# pomodoro.net
KiCad netlist of a schematic drawn in EAGLE
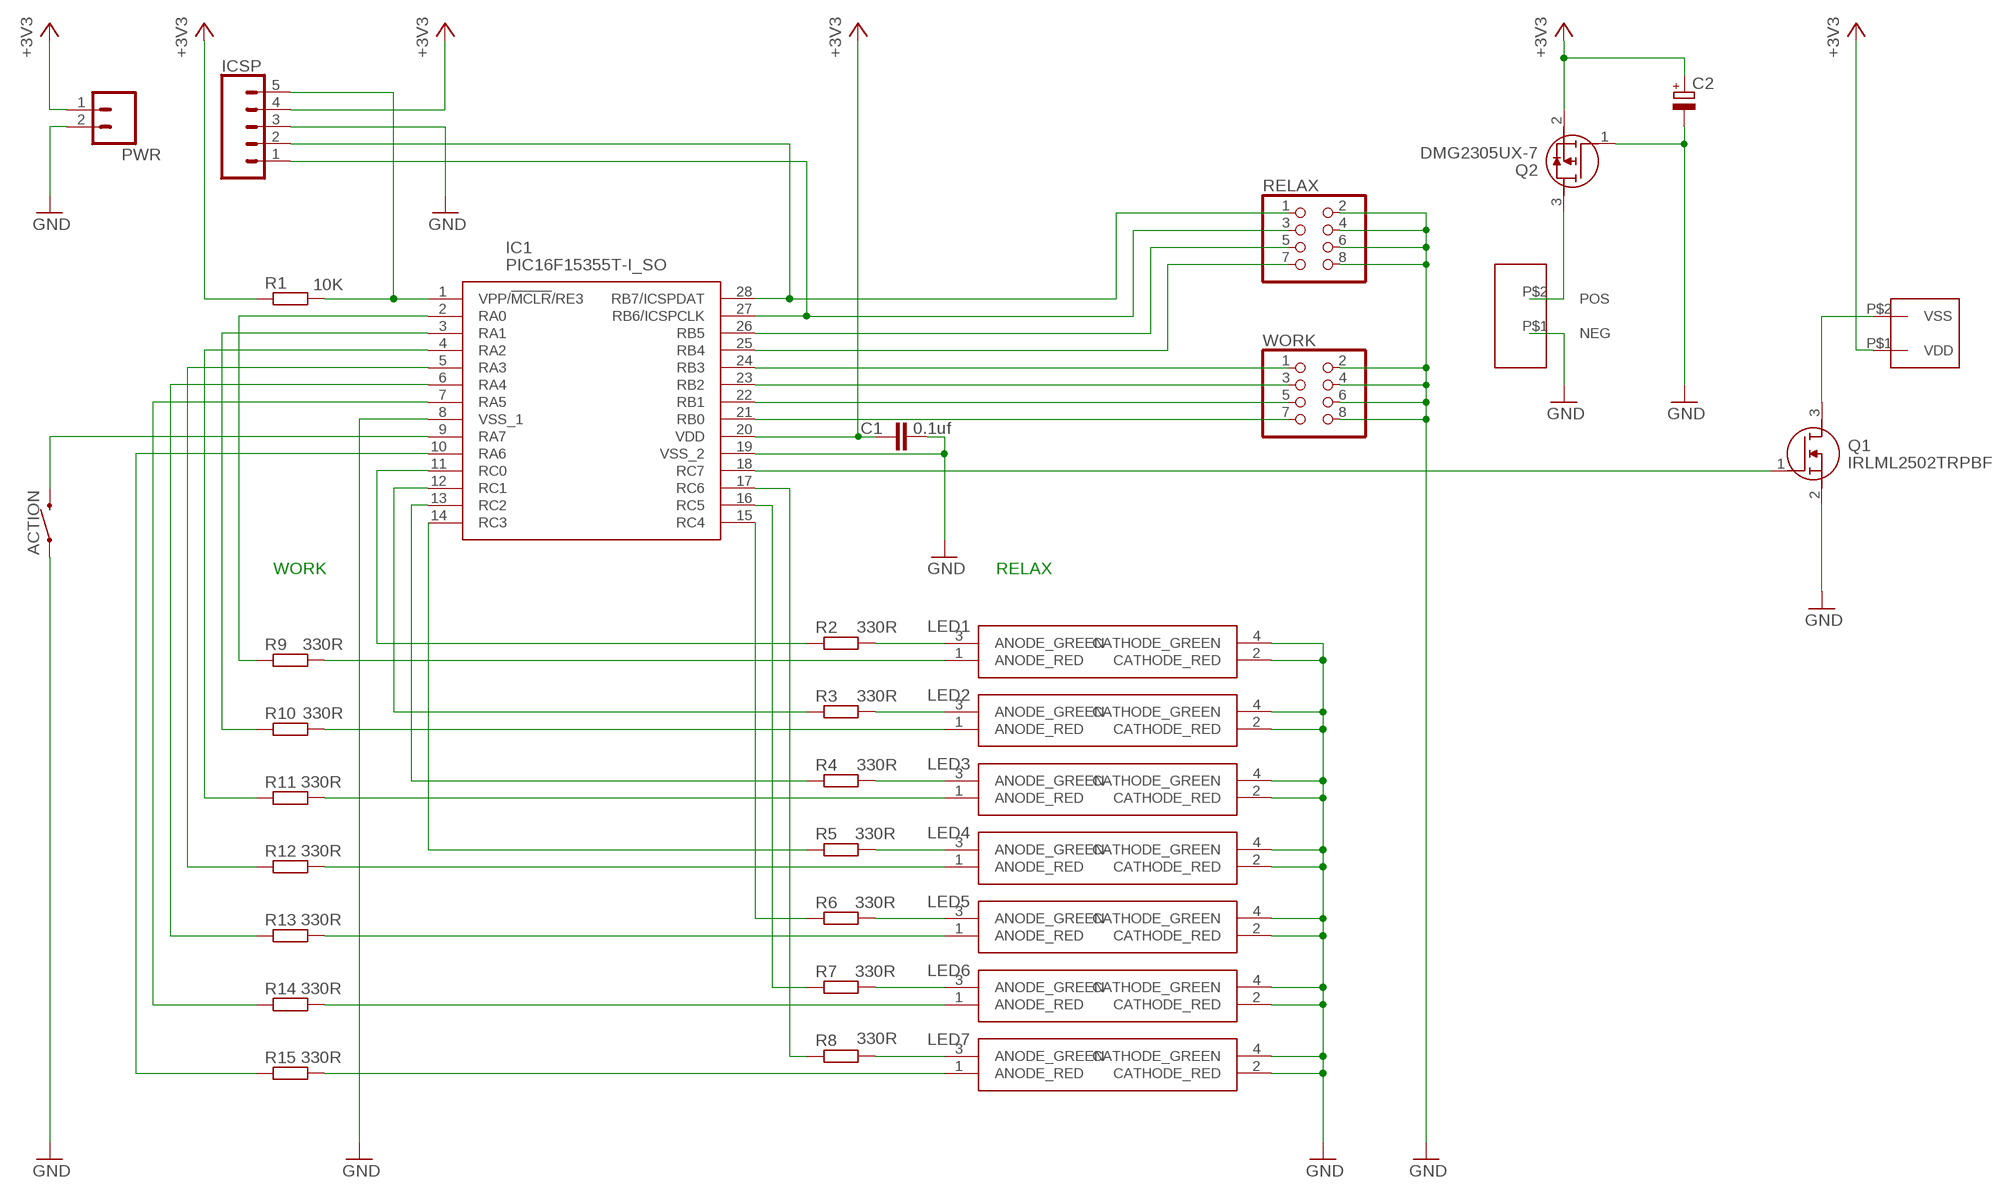
[diagram p0: schematic, sheet 1]

(export (version "E")
  (design (tool "Eeschema 10.0.6"))
  (components
    (comp (ref "ACTION")
      (value "MOMENTARY-SWITCH-SPST-SMD-6.0X3.5MM")
      (footprint "eagle-import:TACTILE_SWITCH_SMD_6.0X3.5MM")
      (libsource (lib "eagle-import") (part "MOMENTARY-SWITCH-SPST-SMD-6.0X3.5MM"))
    )
    (comp (ref "C1")
      (value "0.1uf")
      (footprint "eagle-import:C0805")
      (libsource (lib "eagle-import") (part "C-EUC0805"))
    )
    (comp (ref "C2")
      (value "CPOL-EUE2.5-5")
      (footprint "eagle-import:E2,5-5")
      (libsource (lib "eagle-import") (part "CPOL-EUE2.5-5"))
    )
    (comp (ref "IC1")
      (value "PIC16F15355T-I_SO")
      (footprint "eagle-import:SOIC127P1030X265-28M")
      (fields
        (field (name "MANUFACTURER_PART_NUMBER") "PIC16F15355T-I/SO")
        (field (name "MOUSER_PART_NUMBER") "579-PIC16F15355TI/SO")
      )
      (libsource (lib "eagle-import") (part "PIC16F15355T-I_SO"))
    )
    (comp (ref "ICSP")
      (value "CONN_05")
      (footprint "eagle-import:1X05")
      (libsource (lib "eagle-import") (part "CONN_05"))
    )
    (comp (ref "LED1")
      (value "APBD3224LSURKCGKC")
      (footprint "eagle-import:APBD3224LSURKCGKC")
      (fields (field (name "MOUSER_PART_NUMBER") "604-APBD3224LSURKCGK"))
      (libsource (lib "eagle-import") (part "APBD3224LSURKCGKC"))
    )
    (comp (ref "LED2")
      (value "APBD3224LSURKCGKC")
      (footprint "eagle-import:APBD3224LSURKCGKC")
      (fields (field (name "MOUSER_PART_NUMBER") "604-APBD3224LSURKCGK"))
      (libsource (lib "eagle-import") (part "APBD3224LSURKCGKC"))
    )
    (comp (ref "LED3")
      (value "APBD3224LSURKCGKC")
      (footprint "eagle-import:APBD3224LSURKCGKC")
      (fields (field (name "MOUSER_PART_NUMBER") "604-APBD3224LSURKCGK"))
      (libsource (lib "eagle-import") (part "APBD3224LSURKCGKC"))
    )
    (comp (ref "LED4")
      (value "APBD3224LSURKCGKC")
      (footprint "eagle-import:APBD3224LSURKCGKC")
      (fields (field (name "MOUSER_PART_NUMBER") "604-APBD3224LSURKCGK"))
      (libsource (lib "eagle-import") (part "APBD3224LSURKCGKC"))
    )
    (comp (ref "LED5")
      (value "APBD3224LSURKCGKC")
      (footprint "eagle-import:APBD3224LSURKCGKC")
      (fields (field (name "MOUSER_PART_NUMBER") "604-APBD3224LSURKCGK"))
      (libsource (lib "eagle-import") (part "APBD3224LSURKCGKC"))
    )
    (comp (ref "LED6")
      (value "APBD3224LSURKCGKC")
      (footprint "eagle-import:APBD3224LSURKCGKC")
      (fields (field (name "MOUSER_PART_NUMBER") "604-APBD3224LSURKCGK"))
      (libsource (lib "eagle-import") (part "APBD3224LSURKCGKC"))
    )
    (comp (ref "LED7")
      (value "APBD3224LSURKCGKC")
      (footprint "eagle-import:APBD3224LSURKCGKC")
      (fields (field (name "MOUSER_PART_NUMBER") "604-APBD3224LSURKCGK"))
      (libsource (lib "eagle-import") (part "APBD3224LSURKCGKC"))
    )
    (comp (ref "PWR")
      (value "CONN_02")
      (footprint "eagle-import:1X02")
      (libsource (lib "eagle-import") (part "CONN_02"))
    )
    (comp (ref "Q1")
      (value "IRLML2502TRPBF")
      (footprint "eagle-import:SOT95P237X112-3N")
      (fields (field (name "MOUSER_PART_NUMBER") "942-IRLML2502TRPBF"))
      (libsource (lib "eagle-import") (part "IRLML2502TRPBF"))
    )
    (comp (ref "Q2")
      (value "DMG2305UX-7")
      (footprint "eagle-import:SOT96P240X115-3N")
      (fields (field (name "MOUSER_PART_NUMBER") "621-DMG2305UX-7"))
      (libsource (lib "eagle-import") (part "DMG2305UX-7"))
    )
    (comp (ref "R1")
      (value "10K")
      (footprint "eagle-import:R0805")
      (libsource (lib "eagle-import") (part "R-EU_R0805"))
    )
    (comp (ref "R2")
      (value "330R")
      (footprint "eagle-import:R0805")
      (libsource (lib "eagle-import") (part "R-EU_R0805"))
    )
    (comp (ref "R3")
      (value "330R")
      (footprint "eagle-import:R0805")
      (libsource (lib "eagle-import") (part "R-EU_R0805"))
    )
    (comp (ref "R4")
      (value "330R")
      (footprint "eagle-import:R0805")
      (libsource (lib "eagle-import") (part "R-EU_R0805"))
    )
    (comp (ref "R5")
      (value "330R")
      (footprint "eagle-import:R0805")
      (libsource (lib "eagle-import") (part "R-EU_R0805"))
    )
    (comp (ref "R6")
      (value "330R")
      (footprint "eagle-import:R0805")
      (libsource (lib "eagle-import") (part "R-EU_R0805"))
    )
    (comp (ref "R7")
      (value "330R")
      (footprint "eagle-import:R0805")
      (libsource (lib "eagle-import") (part "R-EU_R0805"))
    )
    (comp (ref "R8")
      (value "330R")
      (footprint "eagle-import:R0805")
      (libsource (lib "eagle-import") (part "R-EU_R0805"))
    )
    (comp (ref "R9")
      (value "330R")
      (footprint "eagle-import:R0805")
      (libsource (lib "eagle-import") (part "R-EU_R0805"))
    )
    (comp (ref "R10")
      (value "330R")
      (footprint "eagle-import:R0805")
      (libsource (lib "eagle-import") (part "R-EU_R0805"))
    )
    (comp (ref "R11")
      (value "330R")
      (footprint "eagle-import:R0805")
      (libsource (lib "eagle-import") (part "R-EU_R0805"))
    )
    (comp (ref "R12")
      (value "330R")
      (footprint "eagle-import:R0805")
      (libsource (lib "eagle-import") (part "R-EU_R0805"))
    )
    (comp (ref "R13")
      (value "330R")
      (footprint "eagle-import:R0805")
      (libsource (lib "eagle-import") (part "R-EU_R0805"))
    )
    (comp (ref "R14")
      (value "330R")
      (footprint "eagle-import:R0805")
      (libsource (lib "eagle-import") (part "R-EU_R0805"))
    )
    (comp (ref "R15")
      (value "330R")
      (footprint "eagle-import:R0805")
      (libsource (lib "eagle-import") (part "R-EU_R0805"))
    )
    (comp (ref "RELAX")
      (value "PINHD-2X4")
      (footprint "eagle-import:2X04")
      (libsource (lib "eagle-import") (part "PINHD-2X4"))
    )
    (comp (ref "U$1")
      (value "2AAABATT")
      (footprint "eagle-import:2AAABATTSER")
      (libsource (lib "eagle-import") (part "2AAABATT"))
    )
    (comp (ref "U$2")
      (value "BUZZER8X8")
      (footprint "eagle-import:BUZZER8X8")
      (libsource (lib "eagle-import") (part "BUZZER8X8"))
    )
    (comp (ref "WORK")
      (value "PINHD-2X4")
      (footprint "eagle-import:2X04")
      (libsource (lib "eagle-import") (part "PINHD-2X4"))
    )
  )
  (nets
    (net (code "1") (name "+3V3") (class "Default")
      (node (ref "C1") (pin "1") (pinfunction "1_1") (pintype "passive"))
      (node (ref "C2") (pin "+") (pinfunction "+_+") (pintype "passive"))
      (node (ref "IC1") (pin "20") (pinfunction "VDD_20") (pintype "bidirectional"))
      (node (ref "ICSP") (pin "4") (pinfunction "4_4") (pintype "passive"))
      (node (ref "PWR") (pin "1") (pinfunction "1_1") (pintype "passive"))
      (node (ref "Q2") (pin "2") (pinfunction "S_2") (pintype "bidirectional"))
      (node (ref "R1") (pin "1") (pinfunction "1_1") (pintype "passive"))
      (node (ref "U$2") (pin "P$1") (pinfunction "VDD_P$1") (pintype "bidirectional"))
    )
    (net (code "2") (name "GND") (class "Default")
      (node (ref "ACTION") (pin "1") (pinfunction "1_1") (pintype "passive"))
      (node (ref "C1") (pin "2") (pinfunction "2_2") (pintype "passive"))
      (node (ref "C2") (pin "-") (pinfunction "-_-") (pintype "passive"))
      (node (ref "IC1") (pin "19") (pinfunction "VSS_2_19") (pintype "bidirectional"))
      (node (ref "IC1") (pin "8") (pinfunction "VSS_1_8") (pintype "bidirectional"))
      (node (ref "ICSP") (pin "3") (pinfunction "3_3") (pintype "passive"))
      (node (ref "LED1") (pin "2") (pinfunction "CATHODE_RED_2") (pintype "bidirectional"))
      (node (ref "LED1") (pin "4") (pinfunction "CATHODE_GREEN_4") (pintype "bidirectional"))
      (node (ref "LED2") (pin "2") (pinfunction "CATHODE_RED_2") (pintype "bidirectional"))
      (node (ref "LED2") (pin "4") (pinfunction "CATHODE_GREEN_4") (pintype "bidirectional"))
      (node (ref "LED3") (pin "2") (pinfunction "CATHODE_RED_2") (pintype "bidirectional"))
      (node (ref "LED3") (pin "4") (pinfunction "CATHODE_GREEN_4") (pintype "bidirectional"))
      (node (ref "LED4") (pin "2") (pinfunction "CATHODE_RED_2") (pintype "bidirectional"))
      (node (ref "LED4") (pin "4") (pinfunction "CATHODE_GREEN_4") (pintype "bidirectional"))
      (node (ref "LED5") (pin "2") (pinfunction "CATHODE_RED_2") (pintype "bidirectional"))
      (node (ref "LED5") (pin "4") (pinfunction "CATHODE_GREEN_4") (pintype "bidirectional"))
      (node (ref "LED6") (pin "2") (pinfunction "CATHODE_RED_2") (pintype "bidirectional"))
      (node (ref "LED6") (pin "4") (pinfunction "CATHODE_GREEN_4") (pintype "bidirectional"))
      (node (ref "LED7") (pin "2") (pinfunction "CATHODE_RED_2") (pintype "bidirectional"))
      (node (ref "LED7") (pin "4") (pinfunction "CATHODE_GREEN_4") (pintype "bidirectional"))
      (node (ref "PWR") (pin "2") (pinfunction "2_2") (pintype "passive"))
      (node (ref "Q1") (pin "2") (pinfunction "S_2") (pintype "bidirectional"))
      (node (ref "Q2") (pin "1") (pinfunction "G_1") (pintype "bidirectional"))
      (node (ref "RELAX") (pin "2") (pinfunction "2_2") (pintype "passive"))
      (node (ref "RELAX") (pin "4") (pinfunction "4_4") (pintype "passive"))
      (node (ref "RELAX") (pin "6") (pinfunction "6_6") (pintype "passive"))
      (node (ref "RELAX") (pin "8") (pinfunction "8_8") (pintype "passive"))
      (node (ref "U$1") (pin "P$1") (pinfunction "NEG_P$1") (pintype "power_in"))
      (node (ref "WORK") (pin "2") (pinfunction "2_2") (pintype "passive"))
      (node (ref "WORK") (pin "4") (pinfunction "4_4") (pintype "passive"))
      (node (ref "WORK") (pin "6") (pinfunction "6_6") (pintype "passive"))
      (node (ref "WORK") (pin "8") (pinfunction "8_8") (pintype "passive"))
    )
    (net (code "3") (name "Net-(IC1-RA0)") (class "Default")
      (node (ref "IC1") (pin "2") (pinfunction "RA0_2") (pintype "bidirectional"))
      (node (ref "R9") (pin "1") (pinfunction "1_1") (pintype "passive"))
    )
    (net (code "4") (name "Net-(IC1-RA1)") (class "Default")
      (node (ref "IC1") (pin "3") (pinfunction "RA1_3") (pintype "bidirectional"))
      (node (ref "R10") (pin "1") (pinfunction "1_1") (pintype "passive"))
    )
    (net (code "5") (name "Net-(IC1-RA2)") (class "Default")
      (node (ref "IC1") (pin "4") (pinfunction "RA2_4") (pintype "bidirectional"))
      (node (ref "R11") (pin "1") (pinfunction "1_1") (pintype "passive"))
    )
    (net (code "6") (name "Net-(IC1-RA3)") (class "Default")
      (node (ref "IC1") (pin "5") (pinfunction "RA3_5") (pintype "bidirectional"))
      (node (ref "R12") (pin "1") (pinfunction "1_1") (pintype "passive"))
    )
    (net (code "7") (name "Net-(IC1-RA4)") (class "Default")
      (node (ref "IC1") (pin "6") (pinfunction "RA4_6") (pintype "bidirectional"))
      (node (ref "R13") (pin "1") (pinfunction "1_1") (pintype "passive"))
    )
    (net (code "8") (name "Net-(IC1-RA5)") (class "Default")
      (node (ref "IC1") (pin "7") (pinfunction "RA5_7") (pintype "bidirectional"))
      (node (ref "R14") (pin "1") (pinfunction "1_1") (pintype "passive"))
    )
    (net (code "9") (name "Net-(IC1-RA6)") (class "Default")
      (node (ref "IC1") (pin "10") (pinfunction "RA6_10") (pintype "bidirectional"))
      (node (ref "R15") (pin "1") (pinfunction "1_1") (pintype "passive"))
    )
    (net (code "10") (name "Net-(IC1-RA7)") (class "Default")
      (node (ref "ACTION") (pin "2") (pinfunction "2_2") (pintype "passive"))
      (node (ref "IC1") (pin "9") (pinfunction "RA7_9") (pintype "bidirectional"))
    )
    (net (code "11") (name "Net-(IC1-RB0)") (class "Default")
      (node (ref "IC1") (pin "21") (pinfunction "RB0_21") (pintype "bidirectional"))
      (node (ref "WORK") (pin "7") (pinfunction "7_7") (pintype "passive"))
    )
    (net (code "12") (name "Net-(IC1-RB1)") (class "Default")
      (node (ref "IC1") (pin "22") (pinfunction "RB1_22") (pintype "bidirectional"))
      (node (ref "WORK") (pin "5") (pinfunction "5_5") (pintype "passive"))
    )
    (net (code "13") (name "Net-(IC1-RB2)") (class "Default")
      (node (ref "IC1") (pin "23") (pinfunction "RB2_23") (pintype "bidirectional"))
      (node (ref "WORK") (pin "3") (pinfunction "3_3") (pintype "passive"))
    )
    (net (code "14") (name "Net-(IC1-RB3)") (class "Default")
      (node (ref "IC1") (pin "24") (pinfunction "RB3_24") (pintype "bidirectional"))
      (node (ref "WORK") (pin "1") (pinfunction "1_1") (pintype "passive"))
    )
    (net (code "15") (name "Net-(IC1-RB4)") (class "Default")
      (node (ref "IC1") (pin "25") (pinfunction "RB4_25") (pintype "bidirectional"))
      (node (ref "RELAX") (pin "7") (pinfunction "7_7") (pintype "passive"))
    )
    (net (code "16") (name "Net-(IC1-RB5)") (class "Default")
      (node (ref "IC1") (pin "26") (pinfunction "RB5_26") (pintype "bidirectional"))
      (node (ref "RELAX") (pin "5") (pinfunction "5_5") (pintype "passive"))
    )
    (net (code "17") (name "Net-(IC1-RB6{slash}ICSPCLK)") (class "Default")
      (node (ref "IC1") (pin "27") (pinfunction "RB6/ICSPCLK_27") (pintype "bidirectional"))
      (node (ref "ICSP") (pin "1") (pinfunction "1_1") (pintype "passive"))
      (node (ref "RELAX") (pin "3") (pinfunction "3_3") (pintype "passive"))
    )
    (net (code "18") (name "Net-(IC1-RB7{slash}ICSPDAT)") (class "Default")
      (node (ref "IC1") (pin "28") (pinfunction "RB7/ICSPDAT_28") (pintype "bidirectional"))
      (node (ref "ICSP") (pin "2") (pinfunction "2_2") (pintype "passive"))
      (node (ref "RELAX") (pin "1") (pinfunction "1_1") (pintype "passive"))
    )
    (net (code "19") (name "Net-(IC1-RC0)") (class "Default")
      (node (ref "IC1") (pin "11") (pinfunction "RC0_11") (pintype "bidirectional"))
      (node (ref "R2") (pin "1") (pinfunction "1_1") (pintype "passive"))
    )
    (net (code "20") (name "Net-(IC1-RC1)") (class "Default")
      (node (ref "IC1") (pin "12") (pinfunction "RC1_12") (pintype "bidirectional"))
      (node (ref "R3") (pin "1") (pinfunction "1_1") (pintype "passive"))
    )
    (net (code "21") (name "Net-(IC1-RC2)") (class "Default")
      (node (ref "IC1") (pin "13") (pinfunction "RC2_13") (pintype "bidirectional"))
      (node (ref "R4") (pin "1") (pinfunction "1_1") (pintype "passive"))
    )
    (net (code "22") (name "Net-(IC1-RC3)") (class "Default")
      (node (ref "IC1") (pin "14") (pinfunction "RC3_14") (pintype "bidirectional"))
      (node (ref "R5") (pin "1") (pinfunction "1_1") (pintype "passive"))
    )
    (net (code "23") (name "Net-(IC1-RC4)") (class "Default")
      (node (ref "IC1") (pin "15") (pinfunction "RC4_15") (pintype "bidirectional"))
      (node (ref "R6") (pin "1") (pinfunction "1_1") (pintype "passive"))
    )
    (net (code "24") (name "Net-(IC1-RC5)") (class "Default")
      (node (ref "IC1") (pin "16") (pinfunction "RC5_16") (pintype "bidirectional"))
      (node (ref "R7") (pin "1") (pinfunction "1_1") (pintype "passive"))
    )
    (net (code "25") (name "Net-(IC1-RC6)") (class "Default")
      (node (ref "IC1") (pin "17") (pinfunction "RC6_17") (pintype "bidirectional"))
      (node (ref "R8") (pin "1") (pinfunction "1_1") (pintype "passive"))
    )
    (net (code "26") (name "Net-(IC1-RC7)") (class "Default")
      (node (ref "IC1") (pin "18") (pinfunction "RC7_18") (pintype "bidirectional"))
      (node (ref "Q1") (pin "1") (pinfunction "G_1") (pintype "bidirectional"))
    )
    (net (code "27") (name "Net-(IC1-VPP{slash}~{MCLR}{slash}RE3)") (class "Default")
      (node (ref "IC1") (pin "1") (pinfunction "VPP/~{MCLR}/RE3_1") (pintype "bidirectional"))
      (node (ref "ICSP") (pin "5") (pinfunction "5_5") (pintype "passive"))
      (node (ref "R1") (pin "2") (pinfunction "2_2") (pintype "passive"))
    )
    (net (code "28") (name "Net-(LED1-ANODE_GREEN)") (class "Default")
      (node (ref "LED1") (pin "3") (pinfunction "ANODE_GREEN_3") (pintype "bidirectional"))
      (node (ref "R2") (pin "2") (pinfunction "2_2") (pintype "passive"))
    )
    (net (code "29") (name "Net-(LED1-ANODE_RED)") (class "Default")
      (node (ref "LED1") (pin "1") (pinfunction "ANODE_RED_1") (pintype "bidirectional"))
      (node (ref "R9") (pin "2") (pinfunction "2_2") (pintype "passive"))
    )
    (net (code "30") (name "Net-(LED2-ANODE_GREEN)") (class "Default")
      (node (ref "LED2") (pin "3") (pinfunction "ANODE_GREEN_3") (pintype "bidirectional"))
      (node (ref "R3") (pin "2") (pinfunction "2_2") (pintype "passive"))
    )
    (net (code "31") (name "Net-(LED2-ANODE_RED)") (class "Default")
      (node (ref "LED2") (pin "1") (pinfunction "ANODE_RED_1") (pintype "bidirectional"))
      (node (ref "R10") (pin "2") (pinfunction "2_2") (pintype "passive"))
    )
    (net (code "32") (name "Net-(LED3-ANODE_GREEN)") (class "Default")
      (node (ref "LED3") (pin "3") (pinfunction "ANODE_GREEN_3") (pintype "bidirectional"))
      (node (ref "R4") (pin "2") (pinfunction "2_2") (pintype "passive"))
    )
    (net (code "33") (name "Net-(LED3-ANODE_RED)") (class "Default")
      (node (ref "LED3") (pin "1") (pinfunction "ANODE_RED_1") (pintype "bidirectional"))
      (node (ref "R11") (pin "2") (pinfunction "2_2") (pintype "passive"))
    )
    (net (code "34") (name "Net-(LED4-ANODE_GREEN)") (class "Default")
      (node (ref "LED4") (pin "3") (pinfunction "ANODE_GREEN_3") (pintype "bidirectional"))
      (node (ref "R5") (pin "2") (pinfunction "2_2") (pintype "passive"))
    )
    (net (code "35") (name "Net-(LED4-ANODE_RED)") (class "Default")
      (node (ref "LED4") (pin "1") (pinfunction "ANODE_RED_1") (pintype "bidirectional"))
      (node (ref "R12") (pin "2") (pinfunction "2_2") (pintype "passive"))
    )
    (net (code "36") (name "Net-(LED5-ANODE_GREEN)") (class "Default")
      (node (ref "LED5") (pin "3") (pinfunction "ANODE_GREEN_3") (pintype "bidirectional"))
      (node (ref "R6") (pin "2") (pinfunction "2_2") (pintype "passive"))
    )
    (net (code "37") (name "Net-(LED5-ANODE_RED)") (class "Default")
      (node (ref "LED5") (pin "1") (pinfunction "ANODE_RED_1") (pintype "bidirectional"))
      (node (ref "R13") (pin "2") (pinfunction "2_2") (pintype "passive"))
    )
    (net (code "38") (name "Net-(LED6-ANODE_GREEN)") (class "Default")
      (node (ref "LED6") (pin "3") (pinfunction "ANODE_GREEN_3") (pintype "bidirectional"))
      (node (ref "R7") (pin "2") (pinfunction "2_2") (pintype "passive"))
    )
    (net (code "39") (name "Net-(LED6-ANODE_RED)") (class "Default")
      (node (ref "LED6") (pin "1") (pinfunction "ANODE_RED_1") (pintype "bidirectional"))
      (node (ref "R14") (pin "2") (pinfunction "2_2") (pintype "passive"))
    )
    (net (code "40") (name "Net-(LED7-ANODE_GREEN)") (class "Default")
      (node (ref "LED7") (pin "3") (pinfunction "ANODE_GREEN_3") (pintype "bidirectional"))
      (node (ref "R8") (pin "2") (pinfunction "2_2") (pintype "passive"))
    )
    (net (code "41") (name "Net-(LED7-ANODE_RED)") (class "Default")
      (node (ref "LED7") (pin "1") (pinfunction "ANODE_RED_1") (pintype "bidirectional"))
      (node (ref "R15") (pin "2") (pinfunction "2_2") (pintype "passive"))
    )
    (net (code "42") (name "Net-(Q1-D)") (class "Default")
      (node (ref "Q1") (pin "3") (pinfunction "D_3") (pintype "bidirectional"))
      (node (ref "U$2") (pin "P$2") (pinfunction "VSS_P$2") (pintype "bidirectional"))
    )
    (net (code "43") (name "Net-(Q2-D)") (class "Default")
      (node (ref "Q2") (pin "3") (pinfunction "D_3") (pintype "bidirectional"))
      (node (ref "U$1") (pin "P$2") (pinfunction "POS_P$2") (pintype "power_in"))
    )
  )
)
